# Navboard2.net
KiCad netlist of a schematic drawn in EAGLE
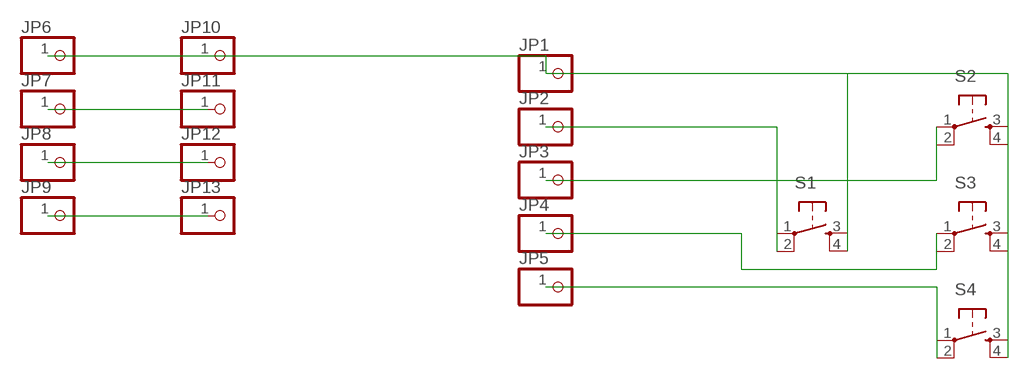
[diagram p0: schematic, sheet 1]

(export (version "E")
  (design (tool "Eeschema 10.0.6"))
  (components
    (comp (ref "JP1")
      (value "PINHD-1X1")
      (footprint "eagle-import:1X01")
      (libsource (lib "eagle-import") (part "PINHD-1X1"))
    )
    (comp (ref "JP2")
      (value "PINHD-1X1")
      (footprint "eagle-import:1X01")
      (libsource (lib "eagle-import") (part "PINHD-1X1"))
    )
    (comp (ref "JP3")
      (value "PINHD-1X1")
      (footprint "eagle-import:1X01")
      (libsource (lib "eagle-import") (part "PINHD-1X1"))
    )
    (comp (ref "JP4")
      (value "PINHD-1X1")
      (footprint "eagle-import:1X01")
      (libsource (lib "eagle-import") (part "PINHD-1X1"))
    )
    (comp (ref "JP5")
      (value "PINHD-1X1")
      (footprint "eagle-import:1X01")
      (libsource (lib "eagle-import") (part "PINHD-1X1"))
    )
    (comp (ref "JP6")
      (value "PINHD-1X1")
      (footprint "eagle-import:1X01")
      (libsource (lib "eagle-import") (part "PINHD-1X1"))
    )
    (comp (ref "JP7")
      (value "PINHD-1X1")
      (footprint "eagle-import:1X01")
      (libsource (lib "eagle-import") (part "PINHD-1X1"))
    )
    (comp (ref "JP8")
      (value "PINHD-1X1")
      (footprint "eagle-import:1X01")
      (libsource (lib "eagle-import") (part "PINHD-1X1"))
    )
    (comp (ref "JP9")
      (value "PINHD-1X1")
      (footprint "eagle-import:1X01")
      (libsource (lib "eagle-import") (part "PINHD-1X1"))
    )
    (comp (ref "JP10")
      (value "PINHD-1X1")
      (footprint "eagle-import:1X01")
      (libsource (lib "eagle-import") (part "PINHD-1X1"))
    )
    (comp (ref "JP11")
      (value "PINHD-1X1")
      (footprint "eagle-import:1X01")
      (libsource (lib "eagle-import") (part "PINHD-1X1"))
    )
    (comp (ref "JP12")
      (value "PINHD-1X1")
      (footprint "eagle-import:1X01")
      (libsource (lib "eagle-import") (part "PINHD-1X1"))
    )
    (comp (ref "JP13")
      (value "PINHD-1X1")
      (footprint "eagle-import:1X01")
      (libsource (lib "eagle-import") (part "PINHD-1X1"))
    )
    (comp (ref "S1")
      (value "TAC_SWITCHPTH")
      (footprint "eagle-import:TACTILE-PTH")
      (libsource (lib "eagle-import") (part "TAC_SWITCHPTH"))
    )
    (comp (ref "S2")
      (value "TAC_SWITCHPTH")
      (footprint "eagle-import:TACTILE-PTH")
      (libsource (lib "eagle-import") (part "TAC_SWITCHPTH"))
    )
    (comp (ref "S3")
      (value "TAC_SWITCHPTH")
      (footprint "eagle-import:TACTILE-PTH")
      (libsource (lib "eagle-import") (part "TAC_SWITCHPTH"))
    )
    (comp (ref "S4")
      (value "TAC_SWITCHPTH")
      (footprint "eagle-import:TACTILE-PTH")
      (libsource (lib "eagle-import") (part "TAC_SWITCHPTH"))
    )
  )
  (nets
    (net (code "1") (name "Net-(JP1-Pad1)") (class "Default")
      (node (ref "JP1") (pin "1") (pinfunction "1_1") (pintype "passive"))
      (node (ref "JP10") (pin "1") (pinfunction "1_1") (pintype "passive"))
      (node (ref "JP6") (pin "1") (pinfunction "1_1") (pintype "passive"))
      (node (ref "S1") (pin "3") (pinfunction "3_3") (pintype "passive"))
      (node (ref "S1") (pin "4") (pinfunction "4_4") (pintype "passive"))
      (node (ref "S2") (pin "3") (pinfunction "3_3") (pintype "passive"))
      (node (ref "S2") (pin "4") (pinfunction "4_4") (pintype "passive"))
      (node (ref "S3") (pin "3") (pinfunction "3_3") (pintype "passive"))
      (node (ref "S3") (pin "4") (pinfunction "4_4") (pintype "passive"))
      (node (ref "S4") (pin "3") (pinfunction "3_3") (pintype "passive"))
      (node (ref "S4") (pin "4") (pinfunction "4_4") (pintype "passive"))
    )
    (net (code "2") (name "Net-(JP2-Pad1)") (class "Default")
      (node (ref "JP2") (pin "1") (pinfunction "1_1") (pintype "passive"))
      (node (ref "S1") (pin "1") (pinfunction "1_1") (pintype "passive"))
      (node (ref "S1") (pin "2") (pinfunction "2_2") (pintype "passive"))
    )
    (net (code "3") (name "Net-(JP3-Pad1)") (class "Default")
      (node (ref "JP3") (pin "1") (pinfunction "1_1") (pintype "passive"))
      (node (ref "S2") (pin "1") (pinfunction "1_1") (pintype "passive"))
      (node (ref "S2") (pin "2") (pinfunction "2_2") (pintype "passive"))
    )
    (net (code "4") (name "Net-(JP4-Pad1)") (class "Default")
      (node (ref "JP4") (pin "1") (pinfunction "1_1") (pintype "passive"))
      (node (ref "S3") (pin "1") (pinfunction "1_1") (pintype "passive"))
      (node (ref "S3") (pin "2") (pinfunction "2_2") (pintype "passive"))
    )
    (net (code "5") (name "Net-(JP5-Pad1)") (class "Default")
      (node (ref "JP5") (pin "1") (pinfunction "1_1") (pintype "passive"))
      (node (ref "S4") (pin "1") (pinfunction "1_1") (pintype "passive"))
      (node (ref "S4") (pin "2") (pinfunction "2_2") (pintype "passive"))
    )
    (net (code "6") (name "Net-(JP11-Pad1)") (class "Default")
      (node (ref "JP11") (pin "1") (pinfunction "1_1") (pintype "passive"))
      (node (ref "JP7") (pin "1") (pinfunction "1_1") (pintype "passive"))
    )
    (net (code "7") (name "Net-(JP12-Pad1)") (class "Default")
      (node (ref "JP12") (pin "1") (pinfunction "1_1") (pintype "passive"))
      (node (ref "JP8") (pin "1") (pinfunction "1_1") (pintype "passive"))
    )
    (net (code "8") (name "Net-(JP13-Pad1)") (class "Default")
      (node (ref "JP13") (pin "1") (pinfunction "1_1") (pintype "passive"))
      (node (ref "JP9") (pin "1") (pinfunction "1_1") (pintype "passive"))
    )
  )
)
